# DIFFAMP.net
KiCad netlist of a schematic drawn in Altium Designer
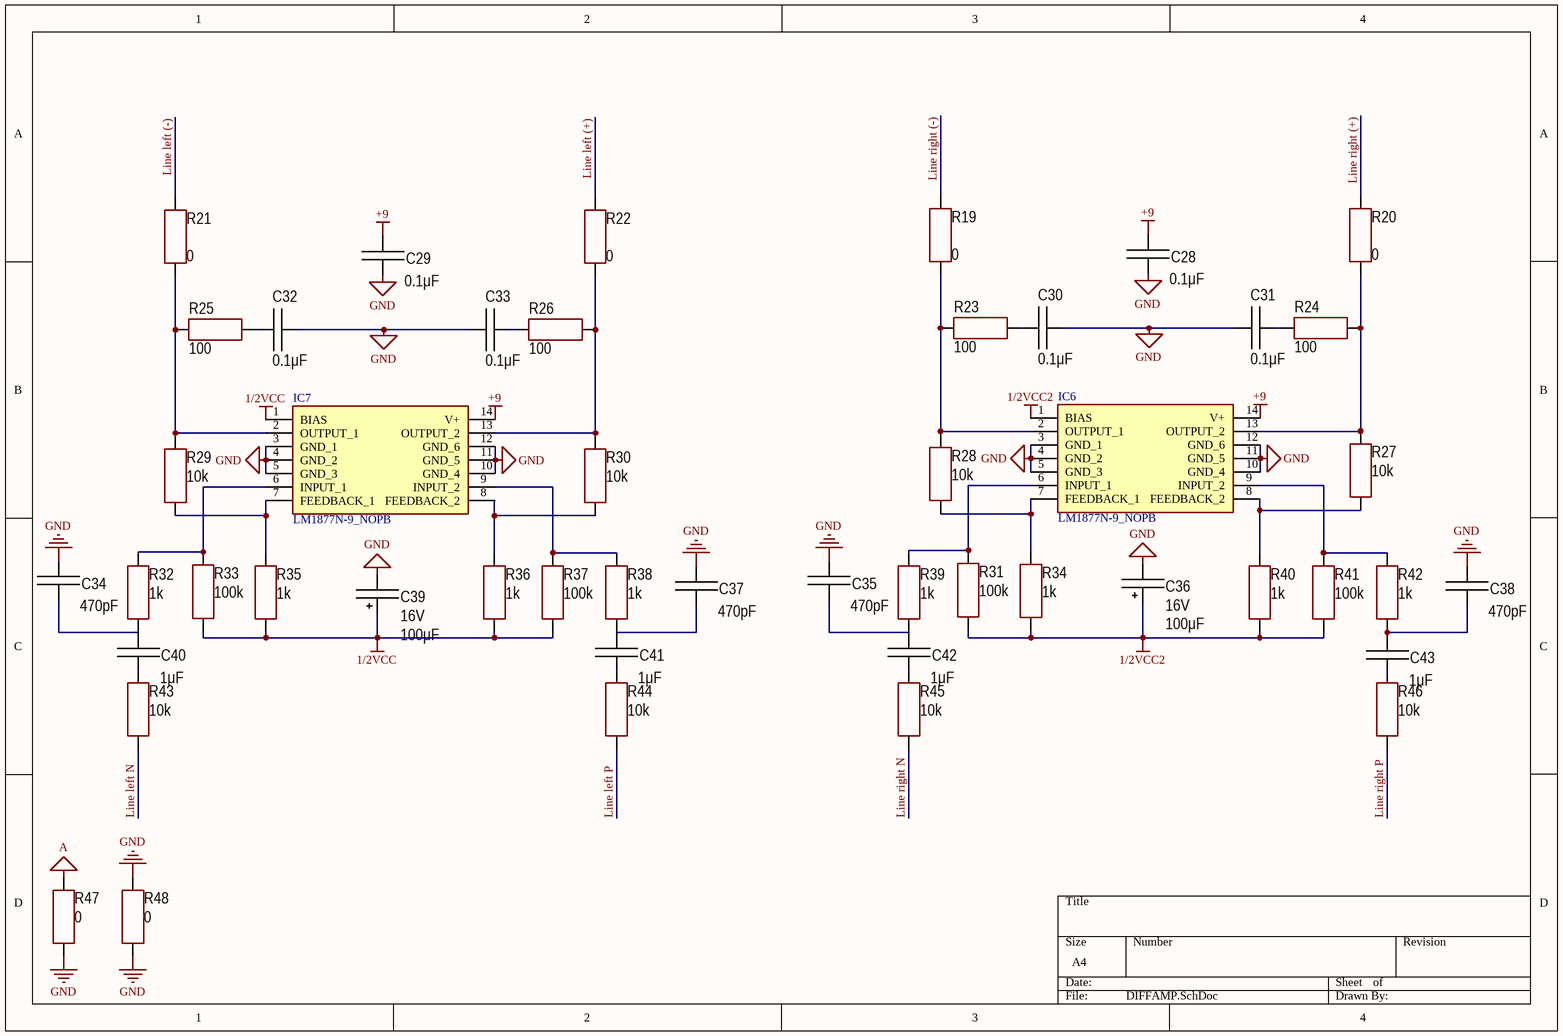
[diagram p0: DIFFAMP.SchDoc]

(export (version "E")
  (design (tool "Eeschema 10.0.6"))
  (components
    (comp (ref "C28")
      (value "0.1μF")
      (footprint "CAP: 0805")
      (fields
        (field (name "MANUFACTURER") "Yageo")
        (field (name "PARTNUMBER") "CC0805KRX7R7BB104")
        (field (name "VALUEMANUFACTURERPARTNUMBER") "Ceramic capacitor, 0.1μF, X7R, ±10%, 16V, 0805, -55...+125°C")
      )
      (libsource (lib "capacitor") (part "Ceramic_0805"))
    )
    (comp (ref "C29")
      (value "0.1μF")
      (footprint "CAP: 0805")
      (fields
        (field (name "MANUFACTURER") "Yageo")
        (field (name "PARTNUMBER") "CC0805KRX7R7BB104")
        (field (name "VALUEMANUFACTURERPARTNUMBER") "Ceramic capacitor, 0.1μF, X7R, ±10%, 16V, 0805, -55...+125°C")
      )
      (libsource (lib "capacitor") (part "Ceramic_0805"))
    )
    (comp (ref "C30")
      (value "0.1μF")
      (footprint "CAP: 0805")
      (fields
        (field (name "MANUFACTURER") "Yageo")
        (field (name "PARTNUMBER") "CC0805KRX7R7BB104")
        (field (name "VALUEMANUFACTURERPARTNUMBER") "Ceramic capacitor, 0.1μF, X7R, ±10%, 16V, 0805, -55...+125°C")
      )
      (libsource (lib "capacitor") (part "Ceramic_0805"))
    )
    (comp (ref "C31")
      (value "0.1μF")
      (footprint "CAP: 0805")
      (fields
        (field (name "MANUFACTURER") "Yageo")
        (field (name "PARTNUMBER") "CC0805KRX7R7BB104")
        (field (name "VALUEMANUFACTURERPARTNUMBER") "Ceramic capacitor, 0.1μF, X7R, ±10%, 16V, 0805, -55...+125°C")
      )
      (libsource (lib "capacitor") (part "Ceramic_0805"))
    )
    (comp (ref "C32")
      (value "0.1μF")
      (footprint "CAP: 0805")
      (fields
        (field (name "MANUFACTURER") "Yageo")
        (field (name "PARTNUMBER") "CC0805KRX7R7BB104")
        (field (name "VALUEMANUFACTURERPARTNUMBER") "Ceramic capacitor, 0.1μF, X7R, ±10%, 16V, 0805, -55...+125°C")
      )
      (libsource (lib "capacitor") (part "Ceramic_0805"))
    )
    (comp (ref "C33")
      (value "0.1μF")
      (footprint "CAP: 0805")
      (fields
        (field (name "MANUFACTURER") "Yageo")
        (field (name "PARTNUMBER") "CC0805KRX7R7BB104")
        (field (name "VALUEMANUFACTURERPARTNUMBER") "Ceramic capacitor, 0.1μF, X7R, ±10%, 16V, 0805, -55...+125°C")
      )
      (libsource (lib "capacitor") (part "Ceramic_0805"))
    )
    (comp (ref "C34")
      (value "470pF")
      (footprint "CAP: 0805")
      (fields
        (field (name "MANUFACTURER") "Yageo")
        (field (name "PARTNUMBER") "CC0805KRX7R7BB104")
        (field (name "VALUEMANUFACTURERPARTNUMBER") "Ceramic capacitor, 470pF, X7R, ±10%, 16V, 0805, -55...+125°C")
      )
      (libsource (lib "capacitor") (part "Ceramic_0805"))
    )
    (comp (ref "C35")
      (value "470pF")
      (footprint "CAP: 0805")
      (fields
        (field (name "MANUFACTURER") "Yageo")
        (field (name "PARTNUMBER") "CC0805KRX7R7BB104")
        (field (name "VALUEMANUFACTURERPARTNUMBER") "Ceramic capacitor, 470pF, X7R, ±10%, 16V, 0805, -55...+125°C")
      )
      (libsource (lib "capacitor") (part "Ceramic_0805"))
    )
    (comp (ref "C36")
      (value "100μF")
      (footprint "CAP: TANTAL-D")
      (fields
        (field (name "MANUFACTURER") "AVX")
        (field (name "PARTNUMBER") "TAJD476M035RNJV")
        (field (name "VALUEMANUFACTURERPARTNUMBER") "Tantalum capacitor, 100μF, 16V, ±20%, 900mOhm, case D (7343), -55...+125°C")
        (field (name "VOLTAGE") "16V")
      )
      (libsource (lib "capacitor") (part "Tantal_D"))
    )
    (comp (ref "C37")
      (value "470pF")
      (footprint "CAP: 0805")
      (fields
        (field (name "MANUFACTURER") "Yageo")
        (field (name "PARTNUMBER") "CC0805KRX7R7BB104")
        (field (name "VALUEMANUFACTURERPARTNUMBER") "Ceramic capacitor, 470pF, X7R, ±10%, 16V, 0805, -55...+125°C")
      )
      (libsource (lib "capacitor") (part "Ceramic_0805"))
    )
    (comp (ref "C38")
      (value "470pF")
      (footprint "CAP: 0805")
      (fields
        (field (name "MANUFACTURER") "Yageo")
        (field (name "PARTNUMBER") "CC0805KRX7R7BB104")
        (field (name "VALUEMANUFACTURERPARTNUMBER") "Ceramic capacitor, 470pF, X7R, ±10%, 16V, 0805, -55...+125°C")
      )
      (libsource (lib "capacitor") (part "Ceramic_0805"))
    )
    (comp (ref "C39")
      (value "100μF")
      (footprint "CAP: TANTAL-D")
      (fields
        (field (name "MANUFACTURER") "AVX")
        (field (name "PARTNUMBER") "TAJD476M035RNJV")
        (field (name "VALUEMANUFACTURERPARTNUMBER") "Tantalum capacitor, 100μF, 16V, ±20%, 900mOhm, case D (7343), -55...+125°C")
        (field (name "VOLTAGE") "16V")
      )
      (libsource (lib "capacitor") (part "Tantal_D"))
    )
    (comp (ref "C40")
      (value "1μF")
      (footprint "CAP: 0805")
      (fields
        (field (name "MANUFACTURER") "Yageo")
        (field (name "PARTNUMBER") "CC0805KRX7R7BB104")
        (field (name "VALUEMANUFACTURERPARTNUMBER") "Ceramic capacitor, 1μF, X7R, ±10%, 16V, 0805, -55...+125°C")
      )
      (libsource (lib "capacitor") (part "Ceramic_0805"))
    )
    (comp (ref "C41")
      (value "1μF")
      (footprint "CAP: 0805")
      (fields
        (field (name "MANUFACTURER") "Yageo")
        (field (name "PARTNUMBER") "CC0805KRX7R7BB104")
        (field (name "VALUEMANUFACTURERPARTNUMBER") "Ceramic capacitor, 1μF, X7R, ±10%, 16V, 0805, -55...+125°C")
      )
      (libsource (lib "capacitor") (part "Ceramic_0805"))
    )
    (comp (ref "C42")
      (value "1μF")
      (footprint "CAP: 0805")
      (fields
        (field (name "MANUFACTURER") "Yageo")
        (field (name "PARTNUMBER") "CC0805KRX7R7BB104")
        (field (name "VALUEMANUFACTURERPARTNUMBER") "Ceramic capacitor, 1μF, X7R, ±10%, 16V, 0805, -55...+125°C")
      )
      (libsource (lib "capacitor") (part "Ceramic_0805"))
    )
    (comp (ref "C43")
      (value "1μF")
      (footprint "CAP: 0805")
      (fields
        (field (name "MANUFACTURER") "Yageo")
        (field (name "PARTNUMBER") "CC0805KRX7R7BB104")
        (field (name "VALUEMANUFACTURERPARTNUMBER") "Ceramic capacitor, 1μF, X7R, ±10%, 16V, 0805, -55...+125°C")
      )
      (libsource (lib "capacitor") (part "Ceramic_0805"))
    )
    (comp (ref "IC6")
      (value "LM1877N-9_NOPB")
      (footprint "SamacSys:DIP787W58P254L1918H508Q14N")
      (description "Integrated Circuit")
      (fields (field (name "MANUFACTURER_PART_NUMBER") "LM1877N-9/NOPB"))
      (libsource (lib "SamacSys") (part "LM1877N-9_NOPB"))
    )
    (comp (ref "IC7")
      (value "LM1877N-9_NOPB")
      (footprint "SamacSys:DIP787W58P254L1918H508Q14N")
      (description "Integrated Circuit")
      (fields (field (name "MANUFACTURER_PART_NUMBER") "LM1877N-9/NOPB"))
      (libsource (lib "SamacSys") (part "LM1877N-9_NOPB"))
    )
    (comp (ref "R19")
      (value "0")
      (footprint "RES: 0805")
      (fields
        (field (name "MANUFACTURER") "Yageo")
        (field (name "PARTNUMBER") "RC0805JR-07100RL")
        (field (name "VALUEMANUFACTURERPARTNUMBER") "Resistor film, 0, ±5%, 0805, 0.125W, -55...+125°C")
      )
      (libsource (lib "") (part "Resistor_0805_1"))
    )
    (comp (ref "R20")
      (value "0")
      (footprint "RES: 0805")
      (fields
        (field (name "MANUFACTURER") "Yageo")
        (field (name "PARTNUMBER") "RC0805JR-07100RL")
        (field (name "VALUEMANUFACTURERPARTNUMBER") "Resistor film, 0, ±5%, 0805, 0.125W, -55...+125°C")
      )
      (libsource (lib "") (part "Resistor_0805_1"))
    )
    (comp (ref "R21")
      (value "0")
      (footprint "RES: 0805")
      (fields
        (field (name "MANUFACTURER") "Yageo")
        (field (name "PARTNUMBER") "RC0805JR-07100RL")
        (field (name "VALUEMANUFACTURERPARTNUMBER") "Resistor film, 0, ±5%, 0805, 0.125W, -55...+125°C")
      )
      (libsource (lib "") (part "Resistor_0805_1"))
    )
    (comp (ref "R22")
      (value "0")
      (footprint "RES: 0805")
      (fields
        (field (name "MANUFACTURER") "Yageo")
        (field (name "PARTNUMBER") "RC0805JR-07100RL")
        (field (name "VALUEMANUFACTURERPARTNUMBER") "Resistor film, 0, ±5%, 0805, 0.125W, -55...+125°C")
      )
      (libsource (lib "") (part "Resistor_0805_1"))
    )
    (comp (ref "R23")
      (value "100")
      (footprint "RES: 0805")
      (fields
        (field (name "MANUFACTURER") "Yageo")
        (field (name "PARTNUMBER") "RC0805JR-07100RL")
        (field (name "VALUEMANUFACTURERPARTNUMBER") "Resistor film, 100, ±5%, 0805, 0.125W, -55...+125°C")
      )
      (libsource (lib "") (part "Resistor_0805_2"))
    )
    (comp (ref "R24")
      (value "100")
      (footprint "RES: 0805")
      (fields
        (field (name "MANUFACTURER") "Yageo")
        (field (name "PARTNUMBER") "RC0805JR-07100RL")
        (field (name "VALUEMANUFACTURERPARTNUMBER") "Resistor film, 100, ±5%, 0805, 0.125W, -55...+125°C")
      )
      (libsource (lib "") (part "Resistor_0805_2"))
    )
    (comp (ref "R25")
      (value "100")
      (footprint "RES: 0805")
      (fields
        (field (name "MANUFACTURER") "Yageo")
        (field (name "PARTNUMBER") "RC0805JR-07100RL")
        (field (name "VALUEMANUFACTURERPARTNUMBER") "Resistor film, 100, ±5%, 0805, 0.125W, -55...+125°C")
      )
      (libsource (lib "") (part "Resistor_0805_2"))
    )
    (comp (ref "R26")
      (value "100")
      (footprint "RES: 0805")
      (fields
        (field (name "MANUFACTURER") "Yageo")
        (field (name "PARTNUMBER") "RC0805JR-07100RL")
        (field (name "VALUEMANUFACTURERPARTNUMBER") "Resistor film, 100, ±5%, 0805, 0.125W, -55...+125°C")
      )
      (libsource (lib "") (part "Resistor_0805_2"))
    )
    (comp (ref "R27")
      (value "10k")
      (footprint "RES: 0805")
      (fields
        (field (name "MANUFACTURER") "Yageo")
        (field (name "PARTNUMBER") "RC0805JR-07100RL")
        (field (name "VALUEMANUFACTURERPARTNUMBER") "Resistor film, 10k, ±5%, 0805, 0.125W, -55...+125°C")
      )
      (libsource (lib "resistor") (part "Resistor_0805"))
    )
    (comp (ref "R28")
      (value "10k")
      (footprint "RES: 0805")
      (fields
        (field (name "MANUFACTURER") "Yageo")
        (field (name "PARTNUMBER") "RC0805JR-07100RL")
        (field (name "VALUEMANUFACTURERPARTNUMBER") "Resistor film, 10k, ±5%, 0805, 0.125W, -55...+125°C")
      )
      (libsource (lib "resistor") (part "Resistor_0805"))
    )
    (comp (ref "R29")
      (value "10k")
      (footprint "RES: 0805")
      (fields
        (field (name "MANUFACTURER") "Yageo")
        (field (name "PARTNUMBER") "RC0805JR-07100RL")
        (field (name "VALUEMANUFACTURERPARTNUMBER") "Resistor film, 10k, ±5%, 0805, 0.125W, -55...+125°C")
      )
      (libsource (lib "resistor") (part "Resistor_0805"))
    )
    (comp (ref "R30")
      (value "10k")
      (footprint "RES: 0805")
      (fields
        (field (name "MANUFACTURER") "Yageo")
        (field (name "PARTNUMBER") "RC0805JR-07100RL")
        (field (name "VALUEMANUFACTURERPARTNUMBER") "Resistor film, 10k, ±5%, 0805, 0.125W, -55...+125°C")
      )
      (libsource (lib "resistor") (part "Resistor_0805"))
    )
    (comp (ref "R31")
      (value "100k")
      (footprint "RES: 0805")
      (fields
        (field (name "MANUFACTURER") "Yageo")
        (field (name "PARTNUMBER") "RC0805JR-07100RL")
        (field (name "VALUEMANUFACTURERPARTNUMBER") "Resistor film, 100k, ±5%, 0805, 0.125W, -55...+125°C")
      )
      (libsource (lib "resistor") (part "Resistor_0805"))
    )
    (comp (ref "R32")
      (value "1k")
      (footprint "RES: 0805")
      (fields
        (field (name "MANUFACTURER") "Yageo")
        (field (name "PARTNUMBER") "RC0805JR-07100RL")
        (field (name "VALUEMANUFACTURERPARTNUMBER") "Resistor film, 1k, ±5%, 0805, 0.125W, -55...+125°C")
      )
      (libsource (lib "resistor") (part "Resistor_0805"))
    )
    (comp (ref "R33")
      (value "100k")
      (footprint "RES: 0805")
      (fields
        (field (name "MANUFACTURER") "Yageo")
        (field (name "PARTNUMBER") "RC0805JR-07100RL")
        (field (name "VALUEMANUFACTURERPARTNUMBER") "Resistor film, 100k, ±5%, 0805, 0.125W, -55...+125°C")
      )
      (libsource (lib "resistor") (part "Resistor_0805"))
    )
    (comp (ref "R34")
      (value "1k")
      (footprint "RES: 0805")
      (fields
        (field (name "MANUFACTURER") "Yageo")
        (field (name "PARTNUMBER") "RC0805JR-07100RL")
        (field (name "VALUEMANUFACTURERPARTNUMBER") "Resistor film, 1k, ±5%, 0805, 0.125W, -55...+125°C")
      )
      (libsource (lib "resistor") (part "Resistor_0805"))
    )
    (comp (ref "R35")
      (value "1k")
      (footprint "RES: 0805")
      (fields
        (field (name "MANUFACTURER") "Yageo")
        (field (name "PARTNUMBER") "RC0805JR-07100RL")
        (field (name "VALUEMANUFACTURERPARTNUMBER") "Resistor film, 1k, ±5%, 0805, 0.125W, -55...+125°C")
      )
      (libsource (lib "resistor") (part "Resistor_0805"))
    )
    (comp (ref "R36")
      (value "1k")
      (footprint "RES: 0805")
      (fields
        (field (name "MANUFACTURER") "Yageo")
        (field (name "PARTNUMBER") "RC0805JR-07100RL")
        (field (name "VALUEMANUFACTURERPARTNUMBER") "Resistor film, 1k, ±5%, 0805, 0.125W, -55...+125°C")
      )
      (libsource (lib "") (part "Resistor_0805_1"))
    )
    (comp (ref "R37")
      (value "100k")
      (footprint "RES: 0805")
      (fields
        (field (name "MANUFACTURER") "Yageo")
        (field (name "PARTNUMBER") "RC0805JR-07100RL")
        (field (name "VALUEMANUFACTURERPARTNUMBER") "Resistor film, 100k, ±5%, 0805, 0.125W, -55...+125°C")
      )
      (libsource (lib "resistor") (part "Resistor_0805"))
    )
    (comp (ref "R38")
      (value "1k")
      (footprint "RES: 0805")
      (fields
        (field (name "MANUFACTURER") "Yageo")
        (field (name "PARTNUMBER") "RC0805JR-07100RL")
        (field (name "VALUEMANUFACTURERPARTNUMBER") "Resistor film, 1k, ±5%, 0805, 0.125W, -55...+125°C")
      )
      (libsource (lib "resistor") (part "Resistor_0805"))
    )
    (comp (ref "R39")
      (value "1k")
      (footprint "RES: 0805")
      (fields
        (field (name "MANUFACTURER") "Yageo")
        (field (name "PARTNUMBER") "RC0805JR-07100RL")
        (field (name "VALUEMANUFACTURERPARTNUMBER") "Resistor film, 1k, ±5%, 0805, 0.125W, -55...+125°C")
      )
      (libsource (lib "resistor") (part "Resistor_0805"))
    )
    (comp (ref "R40")
      (value "1k")
      (footprint "RES: 0805")
      (fields
        (field (name "MANUFACTURER") "Yageo")
        (field (name "PARTNUMBER") "RC0805JR-07100RL")
        (field (name "VALUEMANUFACTURERPARTNUMBER") "Resistor film, 1k, ±5%, 0805, 0.125W, -55...+125°C")
      )
      (libsource (lib "") (part "Resistor_0805_1"))
    )
    (comp (ref "R41")
      (value "100k")
      (footprint "RES: 0805")
      (fields
        (field (name "MANUFACTURER") "Yageo")
        (field (name "PARTNUMBER") "RC0805JR-07100RL")
        (field (name "VALUEMANUFACTURERPARTNUMBER") "Resistor film, 100k, ±5%, 0805, 0.125W, -55...+125°C")
      )
      (libsource (lib "resistor") (part "Resistor_0805"))
    )
    (comp (ref "R42")
      (value "1k")
      (footprint "RES: 0805")
      (fields
        (field (name "MANUFACTURER") "Yageo")
        (field (name "PARTNUMBER") "RC0805JR-07100RL")
        (field (name "VALUEMANUFACTURERPARTNUMBER") "Resistor film, 1k, ±5%, 0805, 0.125W, -55...+125°C")
      )
      (libsource (lib "resistor") (part "Resistor_0805"))
    )
    (comp (ref "R43")
      (value "10k")
      (footprint "RES: 0805")
      (fields
        (field (name "MANUFACTURER") "Yageo")
        (field (name "PARTNUMBER") "RC0805JR-07100RL")
        (field (name "VALUEMANUFACTURERPARTNUMBER") "Resistor film, 10k, ±5%, 0805, 0.125W, -55...+125°C")
      )
      (libsource (lib "resistor") (part "Resistor_0805"))
    )
    (comp (ref "R44")
      (value "10k")
      (footprint "RES: 0805")
      (fields
        (field (name "MANUFACTURER") "Yageo")
        (field (name "PARTNUMBER") "RC0805JR-07100RL")
        (field (name "VALUEMANUFACTURERPARTNUMBER") "Resistor film, 10k, ±5%, 0805, 0.125W, -55...+125°C")
      )
      (libsource (lib "resistor") (part "Resistor_0805"))
    )
    (comp (ref "R45")
      (value "10k")
      (footprint "RES: 0805")
      (fields
        (field (name "MANUFACTURER") "Yageo")
        (field (name "PARTNUMBER") "RC0805JR-07100RL")
        (field (name "VALUEMANUFACTURERPARTNUMBER") "Resistor film, 10k, ±5%, 0805, 0.125W, -55...+125°C")
      )
      (libsource (lib "resistor") (part "Resistor_0805"))
    )
    (comp (ref "R46")
      (value "10k")
      (footprint "RES: 0805")
      (fields
        (field (name "MANUFACTURER") "Yageo")
        (field (name "PARTNUMBER") "RC0805JR-07100RL")
        (field (name "VALUEMANUFACTURERPARTNUMBER") "Resistor film, 10k, ±5%, 0805, 0.125W, -55...+125°C")
      )
      (libsource (lib "resistor") (part "Resistor_0805"))
    )
    (comp (ref "R47")
      (value "0")
      (footprint "RES: 0805")
      (fields
        (field (name "MANUFACTURER") "Yageo")
        (field (name "PARTNUMBER") "RC0805JR-07100RL")
        (field (name "VALUEMANUFACTURERPARTNUMBER") "Resistor film, 0, ±5%, 0805, 0.125W, -55...+125°C")
      )
      (libsource (lib "resistor") (part "Resistor_0805"))
    )
    (comp (ref "R48")
      (value "0")
      (footprint "RES: 0805")
      (fields
        (field (name "MANUFACTURER") "Yageo")
        (field (name "PARTNUMBER") "RC0805JR-07100RL")
        (field (name "VALUEMANUFACTURERPARTNUMBER") "Resistor film, 0, ±5%, 0805, 0.125W, -55...+125°C")
      )
      (libsource (lib "resistor") (part "Resistor_0805"))
    )
  )
  (nets
    (net (code "1") (name "+9") (class "Default")
      (node (ref "C28") (pin "2") (pinfunction "2_2") (pintype "passive"))
      (node (ref "C29") (pin "2") (pinfunction "2_2") (pintype "passive"))
      (node (ref "IC6") (pin "14") (pinfunction "V+_14") (pintype "passive"))
      (node (ref "IC7") (pin "14") (pinfunction "V+_14") (pintype "passive"))
    )
    (net (code "2") (name "/Line left (+)") (class "Default")
      (node (ref "R22") (pin "2") (pinfunction "2_2") (pintype "passive"))
    )
    (net (code "3") (name "/Line left (-)") (class "Default")
      (node (ref "R21") (pin "2") (pinfunction "2_2") (pintype "passive"))
    )
    (net (code "4") (name "/Line left N") (class "Default")
      (node (ref "R43") (pin "2") (pinfunction "2_2") (pintype "passive"))
    )
    (net (code "5") (name "/Line left P") (class "Default")
      (node (ref "R44") (pin "2") (pinfunction "2_2") (pintype "passive"))
    )
    (net (code "6") (name "/Line right (+)") (class "Default")
      (node (ref "R20") (pin "2") (pinfunction "2_2") (pintype "passive"))
    )
    (net (code "7") (name "/Line right (-)") (class "Default")
      (node (ref "R19") (pin "2") (pinfunction "2_2") (pintype "passive"))
    )
    (net (code "8") (name "/Line right N") (class "Default")
      (node (ref "R45") (pin "2") (pinfunction "2_2") (pintype "passive"))
    )
    (net (code "9") (name "/Line right P") (class "Default")
      (node (ref "R46") (pin "2") (pinfunction "2_2") (pintype "passive"))
    )
    (net (code "10") (name "1{slash}2VCC") (class "Default")
      (node (ref "C39") (pin "1") (pinfunction "1_1") (pintype "passive"))
      (node (ref "IC7") (pin "1") (pinfunction "BIAS_1") (pintype "passive"))
      (node (ref "R33") (pin "2") (pinfunction "2_2") (pintype "passive"))
      (node (ref "R35") (pin "2") (pinfunction "2_2") (pintype "passive"))
      (node (ref "R36") (pin "1") (pinfunction "1_1") (pintype "passive"))
      (node (ref "R37") (pin "2") (pinfunction "2_2") (pintype "passive"))
    )
    (net (code "11") (name "1{slash}2VCC2") (class "Default")
      (node (ref "C36") (pin "1") (pinfunction "1_1") (pintype "passive"))
      (node (ref "IC6") (pin "1") (pinfunction "BIAS_1") (pintype "passive"))
      (node (ref "R31") (pin "2") (pinfunction "2_2") (pintype "passive"))
      (node (ref "R34") (pin "2") (pinfunction "2_2") (pintype "passive"))
      (node (ref "R40") (pin "1") (pinfunction "1_1") (pintype "passive"))
      (node (ref "R41") (pin "2") (pinfunction "2_2") (pintype "passive"))
    )
    (net (code "12") (name "A") (class "Default")
      (node (ref "R47") (pin "1") (pinfunction "1_1") (pintype "passive"))
    )
    (net (code "13") (name "GND") (class "Default")
      (node (ref "C28") (pin "1") (pinfunction "1_1") (pintype "passive"))
      (node (ref "C29") (pin "1") (pinfunction "1_1") (pintype "passive"))
      (node (ref "C30") (pin "1") (pinfunction "1_1") (pintype "passive"))
      (node (ref "C31") (pin "1") (pinfunction "1_1") (pintype "passive"))
      (node (ref "C32") (pin "1") (pinfunction "1_1") (pintype "passive"))
      (node (ref "C33") (pin "1") (pinfunction "1_1") (pintype "passive"))
      (node (ref "C34") (pin "2") (pinfunction "2_2") (pintype "passive"))
      (node (ref "C35") (pin "2") (pinfunction "2_2") (pintype "passive"))
      (node (ref "C36") (pin "2") (pinfunction "2_2") (pintype "passive"))
      (node (ref "C37") (pin "2") (pinfunction "2_2") (pintype "passive"))
      (node (ref "C38") (pin "2") (pinfunction "2_2") (pintype "passive"))
      (node (ref "C39") (pin "2") (pinfunction "2_2") (pintype "passive"))
      (node (ref "IC6") (pin "10") (pinfunction "GND_4_10") (pintype "passive"))
      (node (ref "IC6") (pin "11") (pinfunction "GND_5_11") (pintype "passive"))
      (node (ref "IC6") (pin "12") (pinfunction "GND_6_12") (pintype "passive"))
      (node (ref "IC6") (pin "3") (pinfunction "GND_1_3") (pintype "passive"))
      (node (ref "IC6") (pin "4") (pinfunction "GND_2_4") (pintype "passive"))
      (node (ref "IC6") (pin "5") (pinfunction "GND_3_5") (pintype "passive"))
      (node (ref "IC7") (pin "10") (pinfunction "GND_4_10") (pintype "passive"))
      (node (ref "IC7") (pin "11") (pinfunction "GND_5_11") (pintype "passive"))
      (node (ref "IC7") (pin "12") (pinfunction "GND_6_12") (pintype "passive"))
      (node (ref "IC7") (pin "3") (pinfunction "GND_1_3") (pintype "passive"))
      (node (ref "IC7") (pin "4") (pinfunction "GND_2_4") (pintype "passive"))
      (node (ref "IC7") (pin "5") (pinfunction "GND_3_5") (pintype "passive"))
      (node (ref "R47") (pin "2") (pinfunction "2_2") (pintype "passive"))
      (node (ref "R48") (pin "1") (pinfunction "1_1") (pintype "passive"))
      (node (ref "R48") (pin "2") (pinfunction "2_2") (pintype "passive"))
    )
    (net (code "14") (name "Net-(C30-Pad2)") (class "Default")
      (node (ref "C30") (pin "2") (pinfunction "2_2") (pintype "passive"))
      (node (ref "R23") (pin "1") (pinfunction "1_1") (pintype "passive"))
    )
    (net (code "15") (name "Net-(C31-Pad2)") (class "Default")
      (node (ref "C31") (pin "2") (pinfunction "2_2") (pintype "passive"))
      (node (ref "R24") (pin "2") (pinfunction "2_2") (pintype "passive"))
    )
    (net (code "16") (name "Net-(C32-Pad2)") (class "Default")
      (node (ref "C32") (pin "2") (pinfunction "2_2") (pintype "passive"))
      (node (ref "R25") (pin "1") (pinfunction "1_1") (pintype "passive"))
    )
    (net (code "17") (name "Net-(C33-Pad2)") (class "Default")
      (node (ref "C33") (pin "2") (pinfunction "2_2") (pintype "passive"))
      (node (ref "R26") (pin "2") (pinfunction "2_2") (pintype "passive"))
    )
    (net (code "18") (name "Net-(C34-Pad1)") (class "Default")
      (node (ref "C34") (pin "1") (pinfunction "1_1") (pintype "passive"))
      (node (ref "C40") (pin "2") (pinfunction "2_2") (pintype "passive"))
      (node (ref "R32") (pin "2") (pinfunction "2_2") (pintype "passive"))
    )
    (net (code "19") (name "Net-(C35-Pad1)") (class "Default")
      (node (ref "C35") (pin "1") (pinfunction "1_1") (pintype "passive"))
      (node (ref "C42") (pin "2") (pinfunction "2_2") (pintype "passive"))
      (node (ref "R39") (pin "2") (pinfunction "2_2") (pintype "passive"))
    )
    (net (code "20") (name "Net-(C37-Pad1)") (class "Default")
      (node (ref "C37") (pin "1") (pinfunction "1_1") (pintype "passive"))
      (node (ref "C41") (pin "2") (pinfunction "2_2") (pintype "passive"))
      (node (ref "R38") (pin "2") (pinfunction "2_2") (pintype "passive"))
    )
    (net (code "21") (name "Net-(C38-Pad1)") (class "Default")
      (node (ref "C38") (pin "1") (pinfunction "1_1") (pintype "passive"))
      (node (ref "C43") (pin "2") (pinfunction "2_2") (pintype "passive"))
      (node (ref "R42") (pin "2") (pinfunction "2_2") (pintype "passive"))
    )
    (net (code "22") (name "Net-(C40-Pad1)") (class "Default")
      (node (ref "C40") (pin "1") (pinfunction "1_1") (pintype "passive"))
      (node (ref "R43") (pin "1") (pinfunction "1_1") (pintype "passive"))
    )
    (net (code "23") (name "Net-(C41-Pad1)") (class "Default")
      (node (ref "C41") (pin "1") (pinfunction "1_1") (pintype "passive"))
      (node (ref "R44") (pin "1") (pinfunction "1_1") (pintype "passive"))
    )
    (net (code "24") (name "Net-(C42-Pad1)") (class "Default")
      (node (ref "C42") (pin "1") (pinfunction "1_1") (pintype "passive"))
      (node (ref "R45") (pin "1") (pinfunction "1_1") (pintype "passive"))
    )
    (net (code "25") (name "Net-(C43-Pad1)") (class "Default")
      (node (ref "C43") (pin "1") (pinfunction "1_1") (pintype "passive"))
      (node (ref "R46") (pin "1") (pinfunction "1_1") (pintype "passive"))
    )
    (net (code "26") (name "Net-(IC6-FEEDBACK_1)") (class "Default")
      (node (ref "IC6") (pin "7") (pinfunction "FEEDBACK_1_7") (pintype "passive"))
      (node (ref "R28") (pin "2") (pinfunction "2_2") (pintype "passive"))
      (node (ref "R34") (pin "1") (pinfunction "1_1") (pintype "passive"))
    )
    (net (code "27") (name "Net-(IC6-FEEDBACK_2)") (class "Default")
      (node (ref "IC6") (pin "8") (pinfunction "FEEDBACK_2_8") (pintype "passive"))
      (node (ref "R27") (pin "2") (pinfunction "2_2") (pintype "passive"))
      (node (ref "R40") (pin "2") (pinfunction "2_2") (pintype "passive"))
    )
    (net (code "28") (name "Net-(IC6-INPUT_1)") (class "Default")
      (node (ref "IC6") (pin "6") (pinfunction "INPUT_1_6") (pintype "passive"))
      (node (ref "R31") (pin "1") (pinfunction "1_1") (pintype "passive"))
      (node (ref "R39") (pin "1") (pinfunction "1_1") (pintype "passive"))
    )
    (net (code "29") (name "Net-(IC6-INPUT_2)") (class "Default")
      (node (ref "IC6") (pin "9") (pinfunction "INPUT_2_9") (pintype "passive"))
      (node (ref "R41") (pin "1") (pinfunction "1_1") (pintype "passive"))
      (node (ref "R42") (pin "1") (pinfunction "1_1") (pintype "passive"))
    )
    (net (code "30") (name "Net-(IC6-OUTPUT_1)") (class "Default")
      (node (ref "IC6") (pin "2") (pinfunction "OUTPUT_1_2") (pintype "passive"))
      (node (ref "R19") (pin "1") (pinfunction "1_1") (pintype "passive"))
      (node (ref "R23") (pin "2") (pinfunction "2_2") (pintype "passive"))
      (node (ref "R28") (pin "1") (pinfunction "1_1") (pintype "passive"))
    )
    (net (code "31") (name "Net-(IC6-OUTPUT_2)") (class "Default")
      (node (ref "IC6") (pin "13") (pinfunction "OUTPUT_2_13") (pintype "passive"))
      (node (ref "R20") (pin "1") (pinfunction "1_1") (pintype "passive"))
      (node (ref "R24") (pin "1") (pinfunction "1_1") (pintype "passive"))
      (node (ref "R27") (pin "1") (pinfunction "1_1") (pintype "passive"))
    )
    (net (code "32") (name "Net-(IC7-FEEDBACK_1)") (class "Default")
      (node (ref "IC7") (pin "7") (pinfunction "FEEDBACK_1_7") (pintype "passive"))
      (node (ref "R29") (pin "2") (pinfunction "2_2") (pintype "passive"))
      (node (ref "R35") (pin "1") (pinfunction "1_1") (pintype "passive"))
    )
    (net (code "33") (name "Net-(IC7-FEEDBACK_2)") (class "Default")
      (node (ref "IC7") (pin "8") (pinfunction "FEEDBACK_2_8") (pintype "passive"))
      (node (ref "R30") (pin "2") (pinfunction "2_2") (pintype "passive"))
      (node (ref "R36") (pin "2") (pinfunction "2_2") (pintype "passive"))
    )
    (net (code "34") (name "Net-(IC7-INPUT_1)") (class "Default")
      (node (ref "IC7") (pin "6") (pinfunction "INPUT_1_6") (pintype "passive"))
      (node (ref "R32") (pin "1") (pinfunction "1_1") (pintype "passive"))
      (node (ref "R33") (pin "1") (pinfunction "1_1") (pintype "passive"))
    )
    (net (code "35") (name "Net-(IC7-INPUT_2)") (class "Default")
      (node (ref "IC7") (pin "9") (pinfunction "INPUT_2_9") (pintype "passive"))
      (node (ref "R37") (pin "1") (pinfunction "1_1") (pintype "passive"))
      (node (ref "R38") (pin "1") (pinfunction "1_1") (pintype "passive"))
    )
    (net (code "36") (name "Net-(IC7-OUTPUT_1)") (class "Default")
      (node (ref "IC7") (pin "2") (pinfunction "OUTPUT_1_2") (pintype "passive"))
      (node (ref "R21") (pin "1") (pinfunction "1_1") (pintype "passive"))
      (node (ref "R25") (pin "2") (pinfunction "2_2") (pintype "passive"))
      (node (ref "R29") (pin "1") (pinfunction "1_1") (pintype "passive"))
    )
    (net (code "37") (name "Net-(IC7-OUTPUT_2)") (class "Default")
      (node (ref "IC7") (pin "13") (pinfunction "OUTPUT_2_13") (pintype "passive"))
      (node (ref "R22") (pin "1") (pinfunction "1_1") (pintype "passive"))
      (node (ref "R26") (pin "1") (pinfunction "1_1") (pintype "passive"))
      (node (ref "R30") (pin "1") (pinfunction "1_1") (pintype "passive"))
    )
  )
)
